# STM8L001_TX_v2.net
KiCad netlist of a schematic drawn in EAGLE
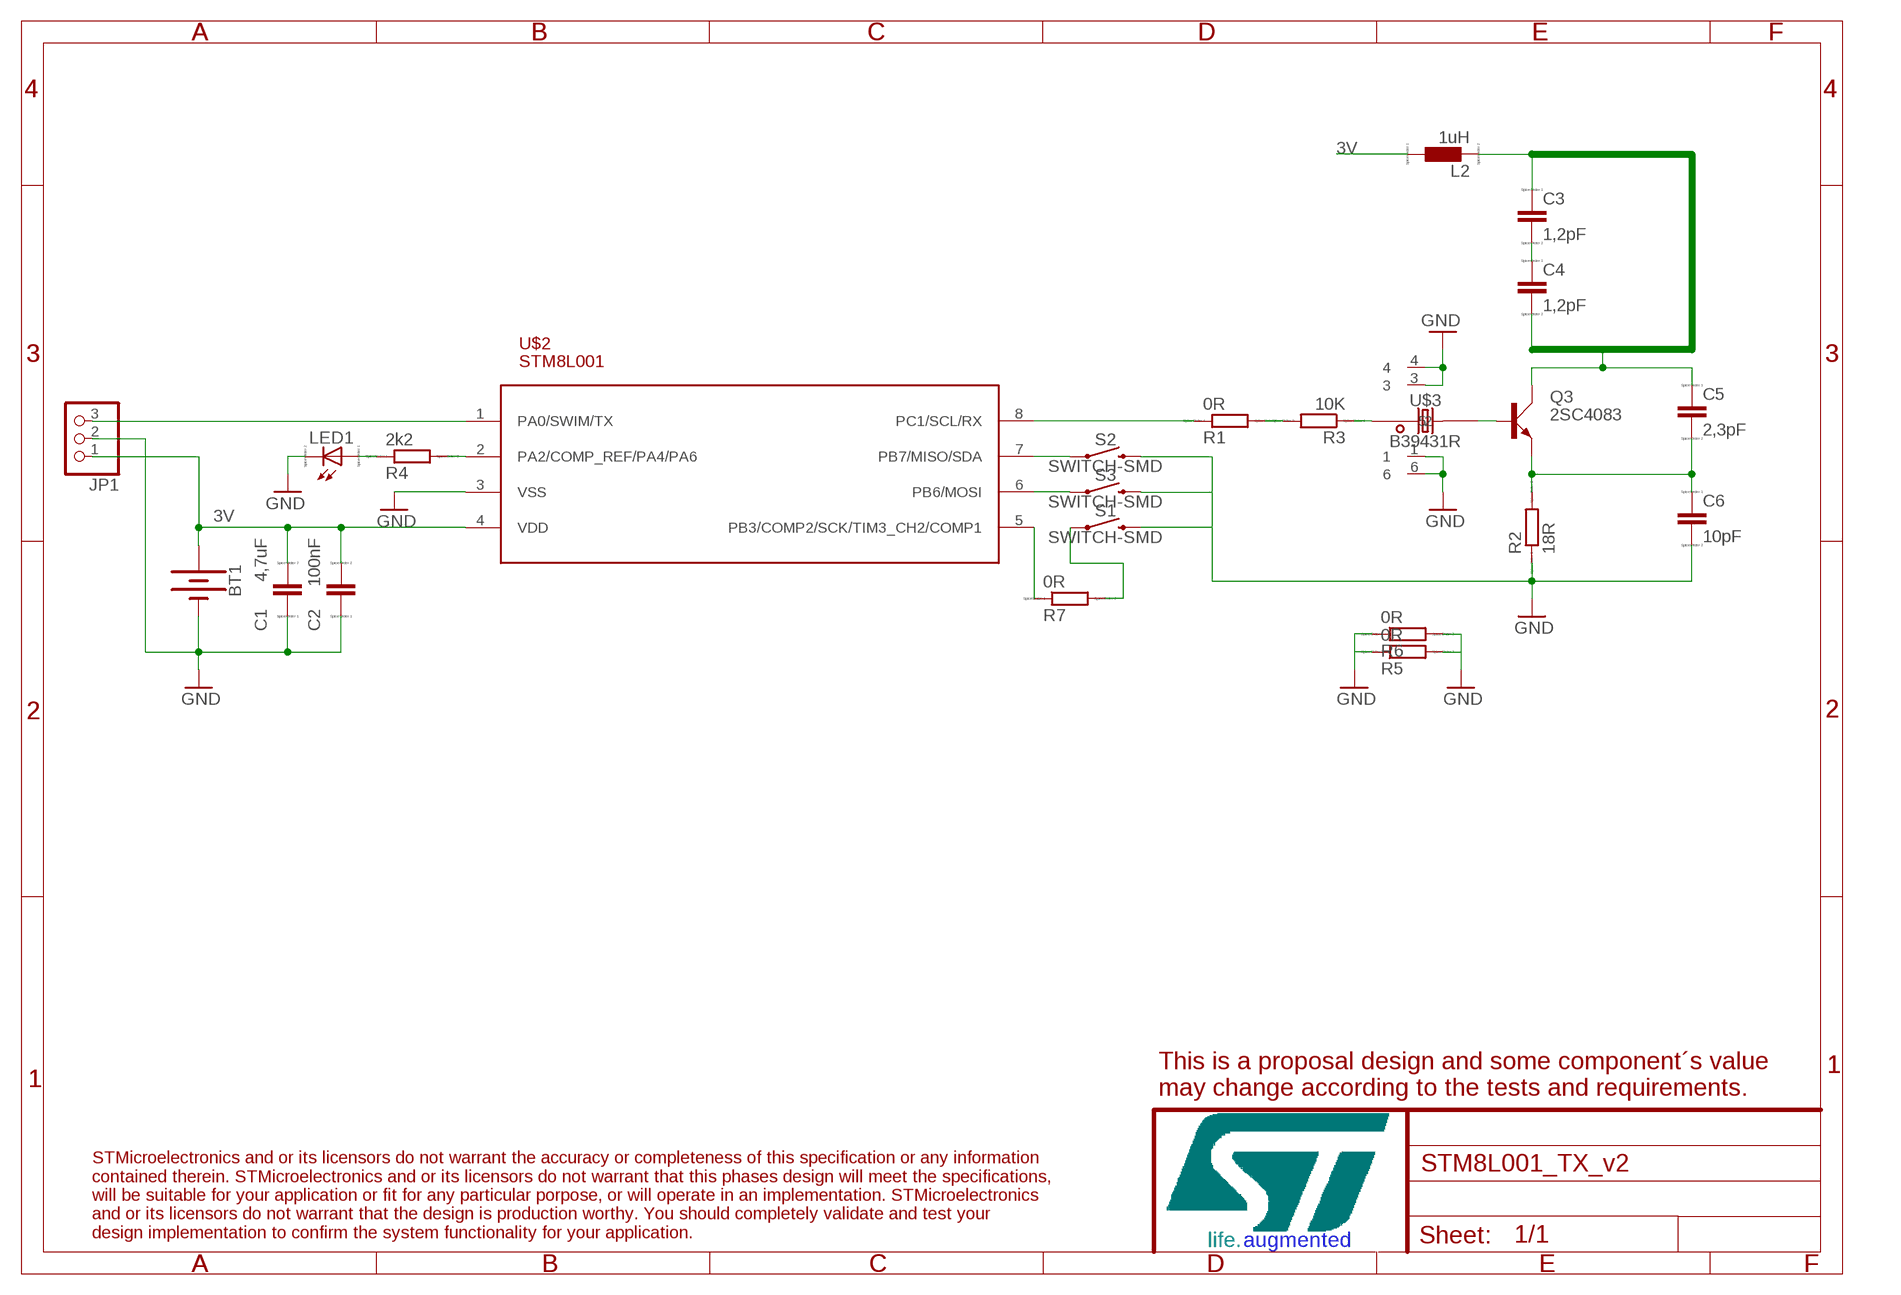
[diagram p0: schematic, sheet 1]

(export (version "E")
  (design (tool "Eeschema 10.0.6"))
  (components
    (comp (ref "BT1")
      (value "BATTERY-20MM_PTH")
      (footprint "eagle-import:BATTCOM_20MM_PTH")
      (libsource (lib "eagle-import") (part "BATTERY-20MM_PTH"))
    )
    (comp (ref "C1")
      (value "4,7uF")
      (footprint "eagle-import:C0603")
      (libsource (lib "eagle-import") (part "CC0603"))
    )
    (comp (ref "C2")
      (value "100nF")
      (footprint "eagle-import:C0603")
      (libsource (lib "eagle-import") (part "CC0603"))
    )
    (comp (ref "C3")
      (value "1,2pF")
      (footprint "eagle-import:C0402")
      (libsource (lib "eagle-import") (part "CC0402"))
    )
    (comp (ref "C4")
      (value "1,2pF")
      (footprint "eagle-import:C0402")
      (libsource (lib "eagle-import") (part "CC0402"))
    )
    (comp (ref "C5")
      (value "2,3pF")
      (footprint "eagle-import:C0402")
      (libsource (lib "eagle-import") (part "CC0402"))
    )
    (comp (ref "C6")
      (value "10pF")
      (footprint "eagle-import:C0402")
      (libsource (lib "eagle-import") (part "CC0402"))
    )
    (comp (ref "JP1")
      (value "PINHD-1X3")
      (footprint "eagle-import:1X03")
      (libsource (lib "eagle-import") (part "PINHD-1X3"))
    )
    (comp (ref "L2")
      (value "1uH")
      (footprint "eagle-import:L3230M")
      (libsource (lib "eagle-import") (part "LL3230M"))
    )
    (comp (ref "LED1")
      (value "LED_ESML0603")
      (footprint "eagle-import:LED_SML0603")
      (libsource (lib "eagle-import") (part "LED_ESML0603"))
    )
    (comp (ref "Q3")
      (value "2SC4083")
      (footprint "eagle-import:UMT3")
      (libsource (lib "eagle-import") (part "2SC4083"))
    )
    (comp (ref "R1")
      (value "0R")
      (footprint "eagle-import:R1206")
      (libsource (lib "eagle-import") (part "RR1206"))
    )
    (comp (ref "R2")
      (value "18R")
      (footprint "eagle-import:R0402")
      (libsource (lib "eagle-import") (part "RR0402"))
    )
    (comp (ref "R3")
      (value "10K")
      (footprint "eagle-import:R0402")
      (libsource (lib "eagle-import") (part "RR0402"))
    )
    (comp (ref "R4")
      (value "2k2")
      (footprint "eagle-import:R1206")
      (libsource (lib "eagle-import") (part "RR1206"))
    )
    (comp (ref "R5")
      (value "0R")
      (footprint "eagle-import:R1206")
      (libsource (lib "eagle-import") (part "RR1206"))
    )
    (comp (ref "R6")
      (value "0R")
      (footprint "eagle-import:R1206")
      (libsource (lib "eagle-import") (part "RR1206"))
    )
    (comp (ref "R7")
      (value "0R")
      (footprint "eagle-import:R1206")
      (libsource (lib "eagle-import") (part "RR1206"))
    )
    (comp (ref "S1")
      (value "SWITCH-SMD")
      (footprint "eagle-import:TACTILE_SWITCH_SMD_6.0X3.5MM")
      (libsource (lib "eagle-import") (part "MOMENTARY-SWITCH-SPST-SMD-6.0X3.5MM"))
    )
    (comp (ref "S2")
      (value "SWITCH-SMD")
      (footprint "eagle-import:TACTILE_SWITCH_SMD_6.0X3.5MM")
      (libsource (lib "eagle-import") (part "MOMENTARY-SWITCH-SPST-SMD-6.0X3.5MM"))
    )
    (comp (ref "S3")
      (value "SWITCH-SMD")
      (footprint "eagle-import:TACTILE_SWITCH_SMD_6.0X3.5MM")
      (libsource (lib "eagle-import") (part "MOMENTARY-SWITCH-SPST-SMD-6.0X3.5MM"))
    )
    (comp (ref "U$2")
      (value "STM8L001")
      (footprint "eagle-import:SO08")
      (libsource (lib "eagle-import") (part "STM8L001"))
    )
    (comp (ref "U$3")
      (value "B39431R")
      (footprint "eagle-import:SON120P300X300X110-6N")
      (libsource (lib "eagle-import") (part "B39431R"))
    )
  )
  (nets
    (net (code "1") (name "/3V") (class "Default")
      (node (ref "BT1") (pin "1") (pinfunction "+_1") (pintype "power_in"))
      (node (ref "C1") (pin "2") (pinfunction "2_2") (pintype "passive"))
      (node (ref "C2") (pin "2") (pinfunction "2_2") (pintype "passive"))
      (node (ref "JP1") (pin "1") (pinfunction "1_1") (pintype "passive"))
      (node (ref "L2") (pin "1") (pinfunction "1_1") (pintype "passive"))
      (node (ref "U$2") (pin "4") (pinfunction "VDD_4") (pintype "bidirectional"))
    )
    (net (code "2") (name "GND") (class "Default")
      (node (ref "BT1") (pin "2") (pinfunction "-_2") (pintype "power_in"))
      (node (ref "C1") (pin "1") (pinfunction "1_1") (pintype "passive"))
      (node (ref "C2") (pin "1") (pinfunction "1_1") (pintype "passive"))
      (node (ref "C6") (pin "2") (pinfunction "2_2") (pintype "passive"))
      (node (ref "JP1") (pin "2") (pinfunction "2_2") (pintype "passive"))
      (node (ref "LED1") (pin "C") (pinfunction "C_C") (pintype "passive"))
      (node (ref "R2") (pin "1") (pinfunction "1_1") (pintype "passive"))
      (node (ref "R5") (pin "1") (pinfunction "1_1") (pintype "passive"))
      (node (ref "R5") (pin "2") (pinfunction "2_2") (pintype "passive"))
      (node (ref "R6") (pin "1") (pinfunction "1_1") (pintype "passive"))
      (node (ref "R6") (pin "2") (pinfunction "2_2") (pintype "passive"))
      (node (ref "S1") (pin "2") (pinfunction "2_2") (pintype "passive"))
      (node (ref "S2") (pin "2") (pinfunction "2_2") (pintype "passive"))
      (node (ref "S3") (pin "2") (pinfunction "2_2") (pintype "passive"))
      (node (ref "U$2") (pin "3") (pinfunction "VSS_3") (pintype "bidirectional"))
      (node (ref "U$3") (pin "1") (pinfunction "1_1") (pintype "bidirectional"))
      (node (ref "U$3") (pin "3") (pinfunction "3_3") (pintype "bidirectional"))
      (node (ref "U$3") (pin "4") (pinfunction "4_4") (pintype "bidirectional"))
      (node (ref "U$3") (pin "6") (pinfunction "6_6") (pintype "bidirectional"))
    )
    (net (code "3") (name "Net-(C3-Pad2)") (class "Default")
      (node (ref "C3") (pin "2") (pinfunction "2_2") (pintype "passive"))
      (node (ref "C4") (pin "1") (pinfunction "1_1") (pintype "passive"))
    )
    (net (code "4") (name "Net-(LED1-PadA)") (class "Default")
      (node (ref "LED1") (pin "A") (pinfunction "A_A") (pintype "passive"))
      (node (ref "R4") (pin "1") (pinfunction "1_1") (pintype "passive"))
    )
    (net (code "5") (name "Net-(Q3-B)") (class "Default")
      (node (ref "Q3") (pin "2") (pinfunction "B_2") (pintype "passive"))
      (node (ref "U$3") (pin "5") (pinfunction "5_5") (pintype "passive"))
    )
    (net (code "6") (name "Net-(Q3-C)") (class "Default")
      (node (ref "C3") (pin "1") (pinfunction "1_1") (pintype "passive"))
      (node (ref "C4") (pin "2") (pinfunction "2_2") (pintype "passive"))
      (node (ref "C5") (pin "1") (pinfunction "1_1") (pintype "passive"))
      (node (ref "L2") (pin "2") (pinfunction "2_2") (pintype "passive"))
      (node (ref "Q3") (pin "3") (pinfunction "C_3") (pintype "passive"))
    )
    (net (code "7") (name "Net-(Q3-E)") (class "Default")
      (node (ref "C5") (pin "2") (pinfunction "2_2") (pintype "passive"))
      (node (ref "C6") (pin "1") (pinfunction "1_1") (pintype "passive"))
      (node (ref "Q3") (pin "1") (pinfunction "E_1") (pintype "passive"))
      (node (ref "R2") (pin "2") (pinfunction "2_2") (pintype "passive"))
    )
    (net (code "8") (name "Net-(R1-Pad2)") (class "Default")
      (node (ref "R1") (pin "2") (pinfunction "2_2") (pintype "passive"))
      (node (ref "R3") (pin "2") (pinfunction "2_2") (pintype "passive"))
    )
    (net (code "9") (name "Net-(R3-Pad1)") (class "Default")
      (node (ref "R3") (pin "1") (pinfunction "1_1") (pintype "passive"))
      (node (ref "U$3") (pin "2") (pinfunction "2_2") (pintype "passive"))
    )
    (net (code "10") (name "Net-(R7-Pad2)") (class "Default")
      (node (ref "R7") (pin "2") (pinfunction "2_2") (pintype "passive"))
      (node (ref "S1") (pin "1") (pinfunction "1_1") (pintype "passive"))
    )
    (net (code "11") (name "Net-(U$2-PA0{slash}SWIM{slash}TX)") (class "Default")
      (node (ref "JP1") (pin "3") (pinfunction "3_3") (pintype "passive"))
      (node (ref "U$2") (pin "1") (pinfunction "PA0/SWIM/TX_1") (pintype "bidirectional"))
    )
    (net (code "12") (name "Net-(U$2-PA2{slash}COMP_REF{slash}PA4{slash}PA6)") (class "Default")
      (node (ref "R4") (pin "2") (pinfunction "2_2") (pintype "passive"))
      (node (ref "U$2") (pin "2") (pinfunction "PA2/COMP_REF/PA4/PA6_2") (pintype "bidirectional"))
    )
    (net (code "13") (name "Net-(U$2-PB3{slash}COMP2{slash}SCK{slash}TIM3_CH2{slash}COMP1)") (class "Default")
      (node (ref "R7") (pin "1") (pinfunction "1_1") (pintype "passive"))
      (node (ref "U$2") (pin "5") (pinfunction "PB3/COMP2/SCK/TIM3_CH2/COMP1_5") (pintype "bidirectional"))
    )
    (net (code "14") (name "Net-(U$2-PB6{slash}MOSI)") (class "Default")
      (node (ref "S3") (pin "1") (pinfunction "1_1") (pintype "passive"))
      (node (ref "U$2") (pin "6") (pinfunction "PB6/MOSI_6") (pintype "bidirectional"))
    )
    (net (code "15") (name "Net-(U$2-PB7{slash}MISO{slash}SDA)") (class "Default")
      (node (ref "S2") (pin "1") (pinfunction "1_1") (pintype "passive"))
      (node (ref "U$2") (pin "7") (pinfunction "PB7/MISO/SDA_7") (pintype "bidirectional"))
    )
    (net (code "16") (name "Net-(U$2-PC1{slash}SCL{slash}RX)") (class "Default")
      (node (ref "R1") (pin "1") (pinfunction "1_1") (pintype "passive"))
      (node (ref "U$2") (pin "8") (pinfunction "PC1/SCL/RX_8") (pintype "bidirectional"))
    )
  )
)
